# Opto_v1.net
KiCad netlist of a schematic drawn in EAGLE
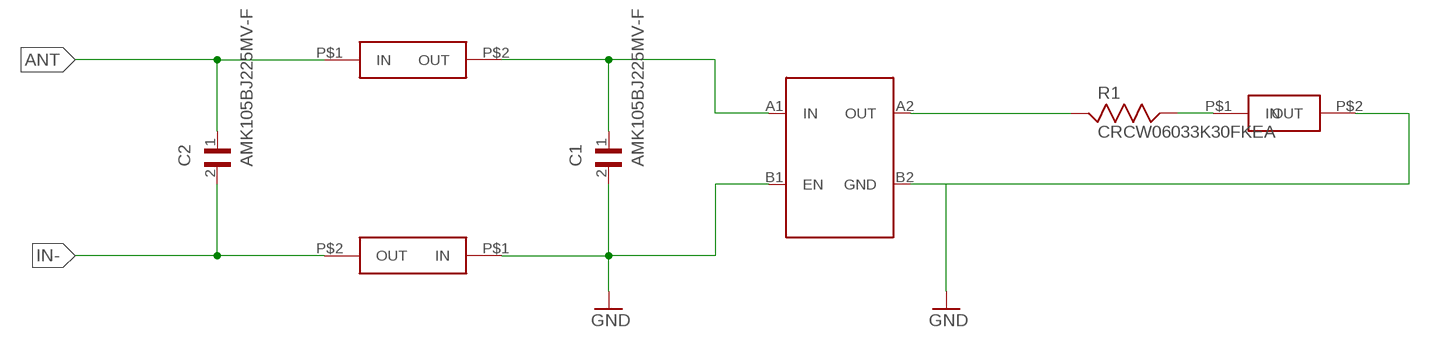
[diagram p0: schematic, sheet 1]

(export (version "E")
  (design (tool "Eeschema 10.0.6"))
  (components
    (comp (ref "C1")
      (value "AMK105BJ225MV-F")
      (footprint "eagle-import:CAPC1005X55N")
      (fields (field (name "MF") "Taiyo Yuden"))
      (libsource (lib "eagle-import") (part "AMK105BJ225MV-F"))
    )
    (comp (ref "C2")
      (value "AMK105BJ225MV-F")
      (footprint "eagle-import:CAPC1005X55N")
      (fields (field (name "MF") "Taiyo Yuden"))
      (libsource (lib "eagle-import") (part "AMK105BJ225MV-F"))
    )
    (comp (ref "R1")
      (value "CRCW06033K30FKEA")
      (footprint "eagle-import:RESC1608X55")
      (fields (field (name "DIGI-KEY_PART_NUMBER") "541-3.30KHCT-ND") (field (name "MF") "Vishay Dale"))
      (libsource (lib "eagle-import") (part "CRCW06033K30FKEA"))
    )
    (comp (ref "U$1")
      (value "BGA4C4")
      (footprint "eagle-import:BGA4C40P2X2_84X84X60N")
      (libsource (lib "eagle-import") (part "BGA4C4"))
    )
    (comp (ref "U$2")
      (value "SCHOTTKY0402")
      (footprint "eagle-import:0402_MURATA")
      (libsource (lib "eagle-import") (part "SCHOTTKY0402"))
    )
    (comp (ref "U$3")
      (value "SCHOTTKY0402")
      (footprint "eagle-import:0402_MURATA")
      (libsource (lib "eagle-import") (part "SCHOTTKY0402"))
    )
    (comp (ref "U$4")
      (value "CREE-TR2227")
      (footprint "eagle-import:CREE-TR2227")
      (libsource (lib "eagle-import") (part "CREE-TR2227"))
    )
  )
  (nets
    (net (code "1") (name "ANT") (class "Default")
      (node (ref "C2") (pin "1") (pinfunction "1_1") (pintype "passive"))
      (node (ref "U$2") (pin "P$1") (pinfunction "IN_P$1") (pintype "bidirectional"))
    )
    (net (code "2") (name "GND") (class "Default")
      (node (ref "C1") (pin "2") (pinfunction "2_2") (pintype "passive"))
      (node (ref "U$1") (pin "B1") (pinfunction "EN_B1") (pintype "bidirectional"))
      (node (ref "U$1") (pin "B2") (pinfunction "GND_B2") (pintype "bidirectional"))
      (node (ref "U$3") (pin "P$1") (pinfunction "IN_P$1") (pintype "bidirectional"))
      (node (ref "U$4") (pin "P$2") (pinfunction "OUT_P$2") (pintype "bidirectional"))
    )
    (net (code "3") (name "IN-") (class "Default")
      (node (ref "C2") (pin "2") (pinfunction "2_2") (pintype "passive"))
      (node (ref "U$3") (pin "P$2") (pinfunction "OUT_P$2") (pintype "bidirectional"))
    )
    (net (code "4") (name "Net-(U$1-IN)") (class "Default")
      (node (ref "C1") (pin "1") (pinfunction "1_1") (pintype "passive"))
      (node (ref "U$1") (pin "A1") (pinfunction "IN_A1") (pintype "bidirectional"))
      (node (ref "U$2") (pin "P$2") (pinfunction "OUT_P$2") (pintype "bidirectional"))
    )
    (net (code "5") (name "Net-(U$1-OUT)") (class "Default")
      (node (ref "R1") (pin "1") (pinfunction "1_1") (pintype "passive"))
      (node (ref "U$1") (pin "A2") (pinfunction "OUT_A2") (pintype "bidirectional"))
    )
    (net (code "6") (name "Net-(U$4-IN)") (class "Default")
      (node (ref "R1") (pin "2") (pinfunction "2_2") (pintype "passive"))
      (node (ref "U$4") (pin "P$1") (pinfunction "IN_P$1") (pintype "bidirectional"))
    )
  )
)
